# Main.net
KiCad netlist of a schematic drawn in Altium Designer
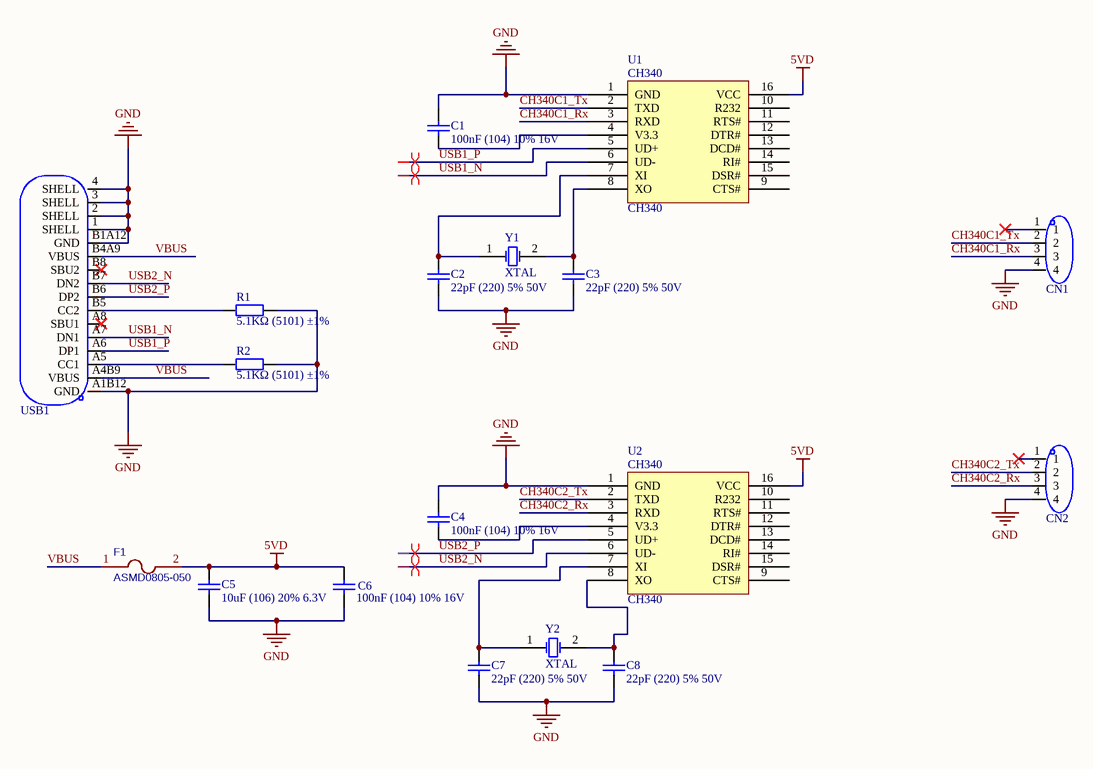
[diagram p0: Main.SchDoc]

(export (version "E")
  (design (tool "Eeschema 10.0.6"))
  (components
    (comp (ref "C1")
      (value "100nF (104) 10% 16V")
      (footprint "0402_C")
      (description "贴片电容")
      (libsource (lib "Cap") (part "0402 100nF (104) 10% 16V"))
    )
    (comp (ref "C2")
      (value "22pF (220) 5% 50V")
      (footprint "0402_C")
      (description "贴片电容")
      (libsource (lib "Miscellaneous Devices LC") (part "0402 22pF (220) 5% 50V"))
    )
    (comp (ref "C3")
      (value "22pF (220) 5% 50V")
      (footprint "0402_C")
      (description "贴片电容")
      (libsource (lib "Miscellaneous Devices LC") (part "0402 22pF (220) 5% 50V"))
    )
    (comp (ref "C4")
      (value "100nF (104) 10% 16V")
      (footprint "0402_C")
      (description "贴片电容")
      (libsource (lib "Cap") (part "0402 100nF (104) 10% 16V"))
    )
    (comp (ref "C5")
      (value "10uF (106) 20% 6.3V")
      (footprint "0402_C")
      (description "贴片电容")
      (libsource (lib "Cap") (part "0402 10uF (106) 20% 6.3V"))
    )
    (comp (ref "C6")
      (value "100nF (104) 10% 16V")
      (footprint "0402_C")
      (description "贴片电容")
      (libsource (lib "Cap") (part "0402 100nF (104) 10% 16V"))
    )
    (comp (ref "C7")
      (value "22pF (220) 5% 50V")
      (footprint "0402_C")
      (description "贴片电容")
      (libsource (lib "Miscellaneous Devices LC") (part "0402 22pF (220) 5% 50V"))
    )
    (comp (ref "C8")
      (value "22pF (220) 5% 50V")
      (footprint "0402_C")
      (description "贴片电容")
      (libsource (lib "Miscellaneous Devices LC") (part "0402 22pF (220) 5% 50V"))
    )
    (comp (ref "CN1")
      (value "1.5-4A")
      (footprint "CONN-TH_1.5-4A")
      (fields (field (name "MANUFACTURER") "CAX(创都)"))
      (libsource (lib "mysch") (part "1.5-4A"))
    )
    (comp (ref "CN2")
      (value "1.5-4A")
      (footprint "CONN-TH_1.5-4A")
      (fields (field (name "MANUFACTURER") "CAX(创都)"))
      (libsource (lib "mysch") (part "1.5-4A"))
    )
    (comp (ref "F1")
      (value "ASMD0805-050")
      (footprint "ASMD0805")
      (fields (field (name "BOM_SUPPLIER PART") "C135329") (field (name "CONTRIBUTOR") "LCSC"))
      (libsource (lib "mysch") (part "ASMD0805-050"))
    )
    (comp (ref "R1")
      (value "5.1KΩ (5101) ±1%")
      (footprint "0402_R")
      (description "贴片电阻")
      (libsource (lib "RES") (part "0402 5.1KΩ (5101) 1%"))
    )
    (comp (ref "R2")
      (value "5.1KΩ (5101) ±1%")
      (footprint "0402_R")
      (description "贴片电阻")
      (libsource (lib "RES") (part "0402 5.1KΩ (5101) 1%"))
    )
    (comp (ref "U1")
      (value "CH340")
      (footprint "SOP-16_L10.0")
      (description "USB to serial")
      (libsource (lib "mysch") (part "CH340"))
    )
    (comp (ref "U2")
      (value "CH340")
      (footprint "SOP-16_L10.0")
      (description "USB to serial")
      (libsource (lib "mysch") (part "CH340"))
    )
    (comp (ref "USB1")
      (value "TYPE-C16PIN")
      (footprint "TYPE-C-SMD")
      (fields (field (name "MANUFACTURER") "SHOU HAN(首韩)"))
      (libsource (lib "mysch") (part "TYPE-C16PIN"))
    )
    (comp (ref "Y1")
      (value "XTAL")
      (footprint "XTAL_socket")
      (description "Crystal Oscillator")
      (fields (field (name "PUBLISHER") "Altium Limited"))
      (libsource (lib "Miscellaneous Devices") (part "XTAL"))
    )
    (comp (ref "Y2")
      (value "XTAL")
      (footprint "XTAL_socket")
      (description "Crystal Oscillator")
      (fields (field (name "PUBLISHER") "Altium Limited"))
      (libsource (lib "Miscellaneous Devices") (part "XTAL"))
    )
  )
  (nets
    (net (code "1") (name "/CH340C1_Rx") (class "Default")
      (node (ref "CN1") (pin "3") (pinfunction "3_3") (pintype "passive"))
      (node (ref "U1") (pin "3") (pinfunction "RXD_3") (pintype "passive"))
    )
    (net (code "2") (name "/CH340C1_Tx") (class "Default")
      (node (ref "CN1") (pin "2") (pinfunction "2_2") (pintype "passive"))
      (node (ref "U1") (pin "2") (pinfunction "TXD_2") (pintype "passive"))
    )
    (net (code "3") (name "/CH340C2_Rx") (class "Default")
      (node (ref "CN2") (pin "3") (pinfunction "3_3") (pintype "passive"))
      (node (ref "U2") (pin "3") (pinfunction "RXD_3") (pintype "passive"))
    )
    (net (code "4") (name "/CH340C2_Tx") (class "Default")
      (node (ref "CN2") (pin "2") (pinfunction "2_2") (pintype "passive"))
      (node (ref "U2") (pin "2") (pinfunction "TXD_2") (pintype "passive"))
    )
    (net (code "5") (name "/USB1_N") (class "Default")
      (node (ref "U1") (pin "6") (pinfunction "UD-_6") (pintype "passive"))
      (node (ref "USB1") (pin "A7") (pinfunction "DN1_A7") (pintype "passive"))
    )
    (net (code "6") (name "/USB1_P") (class "Default")
      (node (ref "U1") (pin "5") (pinfunction "UD+_5") (pintype "passive"))
      (node (ref "USB1") (pin "A6") (pinfunction "DP1_A6") (pintype "passive"))
    )
    (net (code "7") (name "/USB2_N") (class "Default")
      (node (ref "U2") (pin "6") (pinfunction "UD-_6") (pintype "passive"))
      (node (ref "USB1") (pin "B7") (pinfunction "DN2_B7") (pintype "passive"))
    )
    (net (code "8") (name "/USB2_P") (class "Default")
      (node (ref "U2") (pin "5") (pinfunction "UD+_5") (pintype "passive"))
      (node (ref "USB1") (pin "B6") (pinfunction "DP2_B6") (pintype "passive"))
    )
    (net (code "9") (name "/VBUS") (class "Default")
      (node (ref "F1") (pin "1") (pinfunction "1_1") (pintype "passive"))
      (node (ref "USB1") (pin "A4B9") (pinfunction "VBUS_A4B9") (pintype "passive"))
      (node (ref "USB1") (pin "B4A9") (pinfunction "VBUS_B4A9") (pintype "passive"))
    )
    (net (code "10") (name "5VD") (class "Default")
      (node (ref "C5") (pin "2") (pinfunction "2_2") (pintype "passive"))
      (node (ref "C6") (pin "2") (pinfunction "2_2") (pintype "passive"))
      (node (ref "F1") (pin "2") (pinfunction "2_2") (pintype "passive"))
      (node (ref "U1") (pin "16") (pinfunction "VCC_16") (pintype "passive"))
      (node (ref "U2") (pin "16") (pinfunction "VCC_16") (pintype "passive"))
    )
    (net (code "11") (name "GND") (class "Default")
      (node (ref "C1") (pin "2") (pinfunction "2_2") (pintype "passive"))
      (node (ref "C2") (pin "1") (pinfunction "1_1") (pintype "passive"))
      (node (ref "C3") (pin "1") (pinfunction "1_1") (pintype "passive"))
      (node (ref "C4") (pin "2") (pinfunction "2_2") (pintype "passive"))
      (node (ref "C5") (pin "1") (pinfunction "1_1") (pintype "passive"))
      (node (ref "C6") (pin "1") (pinfunction "1_1") (pintype "passive"))
      (node (ref "C7") (pin "1") (pinfunction "1_1") (pintype "passive"))
      (node (ref "C8") (pin "1") (pinfunction "1_1") (pintype "passive"))
      (node (ref "CN1") (pin "4") (pinfunction "4_4") (pintype "passive"))
      (node (ref "CN2") (pin "4") (pinfunction "4_4") (pintype "passive"))
      (node (ref "R1") (pin "2") (pinfunction "2_2") (pintype "passive"))
      (node (ref "R2") (pin "2") (pinfunction "2_2") (pintype "passive"))
      (node (ref "U1") (pin "1") (pinfunction "GND_1") (pintype "passive"))
      (node (ref "U2") (pin "1") (pinfunction "GND_1") (pintype "passive"))
      (node (ref "USB1") (pin "1") (pinfunction "SHELL_1") (pintype "passive"))
      (node (ref "USB1") (pin "2") (pinfunction "SHELL_2") (pintype "passive"))
      (node (ref "USB1") (pin "3") (pinfunction "SHELL_3") (pintype "passive"))
      (node (ref "USB1") (pin "4") (pinfunction "SHELL_4") (pintype "passive"))
      (node (ref "USB1") (pin "A1B12") (pinfunction "GND_A1B12") (pintype "passive"))
      (node (ref "USB1") (pin "B1A12") (pinfunction "GND_B1A12") (pintype "passive"))
    )
    (net (code "12") (name "Net-(U1-V3.3)") (class "Default")
      (node (ref "C1") (pin "1") (pinfunction "1_1") (pintype "passive"))
      (node (ref "U1") (pin "4") (pinfunction "V3.3_4") (pintype "passive"))
    )
    (net (code "13") (name "Net-(U1-XI)") (class "Default")
      (node (ref "C2") (pin "2") (pinfunction "2_2") (pintype "passive"))
      (node (ref "U1") (pin "7") (pinfunction "XI_7") (pintype "passive"))
      (node (ref "Y1") (pin "1") (pinfunction "OSC1_1") (pintype "passive"))
    )
    (net (code "14") (name "Net-(U1-XO)") (class "Default")
      (node (ref "C3") (pin "2") (pinfunction "2_2") (pintype "passive"))
      (node (ref "U1") (pin "8") (pinfunction "XO_8") (pintype "passive"))
      (node (ref "Y1") (pin "2") (pinfunction "OSC2_2") (pintype "passive"))
    )
    (net (code "15") (name "Net-(U2-V3.3)") (class "Default")
      (node (ref "C4") (pin "1") (pinfunction "1_1") (pintype "passive"))
      (node (ref "U2") (pin "4") (pinfunction "V3.3_4") (pintype "passive"))
    )
    (net (code "16") (name "Net-(U2-XI)") (class "Default")
      (node (ref "C7") (pin "2") (pinfunction "2_2") (pintype "passive"))
      (node (ref "U2") (pin "7") (pinfunction "XI_7") (pintype "passive"))
      (node (ref "Y2") (pin "1") (pinfunction "OSC1_1") (pintype "passive"))
    )
    (net (code "17") (name "Net-(U2-XO)") (class "Default")
      (node (ref "C8") (pin "2") (pinfunction "2_2") (pintype "passive"))
      (node (ref "U2") (pin "8") (pinfunction "XO_8") (pintype "passive"))
      (node (ref "Y2") (pin "2") (pinfunction "OSC2_2") (pintype "passive"))
    )
    (net (code "18") (name "Net-(USB1-CC1)") (class "Default")
      (node (ref "R2") (pin "1") (pinfunction "1_1") (pintype "passive"))
      (node (ref "USB1") (pin "A5") (pinfunction "CC1_A5") (pintype "passive"))
    )
    (net (code "19") (name "Net-(USB1-CC2)") (class "Default")
      (node (ref "R1") (pin "1") (pinfunction "1_1") (pintype "passive"))
      (node (ref "USB1") (pin "B5") (pinfunction "CC2_B5") (pintype "passive"))
    )
    (net (code "20") (name "unconnected-(CN1-Pad1)") (class "Default")
      (node (ref "CN1") (pin "1") (pinfunction "1_1") (pintype "passive+no_connect"))
    )
    (net (code "21") (name "unconnected-(CN2-Pad1)") (class "Default")
      (node (ref "CN2") (pin "1") (pinfunction "1_1") (pintype "passive+no_connect"))
    )
    (net (code "22") (name "unconnected-(U1-CTS#-Pad9)") (class "Default")
      (node (ref "U1") (pin "9") (pinfunction "CTS#_9") (pintype "passive"))
    )
    (net (code "23") (name "unconnected-(U1-DCD#-Pad13)") (class "Default")
      (node (ref "U1") (pin "13") (pinfunction "DCD#_13") (pintype "passive"))
    )
    (net (code "24") (name "unconnected-(U1-DSR#-Pad15)") (class "Default")
      (node (ref "U1") (pin "15") (pinfunction "DSR#_15") (pintype "passive"))
    )
    (net (code "25") (name "unconnected-(U1-DTR#-Pad12)") (class "Default")
      (node (ref "U1") (pin "12") (pinfunction "DTR#_12") (pintype "passive"))
    )
    (net (code "26") (name "unconnected-(U1-R232-Pad10)") (class "Default")
      (node (ref "U1") (pin "10") (pinfunction "R232_10") (pintype "passive"))
    )
    (net (code "27") (name "unconnected-(U1-RI#-Pad14)") (class "Default")
      (node (ref "U1") (pin "14") (pinfunction "RI#_14") (pintype "passive"))
    )
    (net (code "28") (name "unconnected-(U1-RTS#-Pad11)") (class "Default")
      (node (ref "U1") (pin "11") (pinfunction "RTS#_11") (pintype "passive"))
    )
    (net (code "29") (name "unconnected-(U2-CTS#-Pad9)") (class "Default")
      (node (ref "U2") (pin "9") (pinfunction "CTS#_9") (pintype "passive"))
    )
    (net (code "30") (name "unconnected-(U2-DCD#-Pad13)") (class "Default")
      (node (ref "U2") (pin "13") (pinfunction "DCD#_13") (pintype "passive"))
    )
    (net (code "31") (name "unconnected-(U2-DSR#-Pad15)") (class "Default")
      (node (ref "U2") (pin "15") (pinfunction "DSR#_15") (pintype "passive"))
    )
    (net (code "32") (name "unconnected-(U2-DTR#-Pad12)") (class "Default")
      (node (ref "U2") (pin "12") (pinfunction "DTR#_12") (pintype "passive"))
    )
    (net (code "33") (name "unconnected-(U2-R232-Pad10)") (class "Default")
      (node (ref "U2") (pin "10") (pinfunction "R232_10") (pintype "passive"))
    )
    (net (code "34") (name "unconnected-(U2-RI#-Pad14)") (class "Default")
      (node (ref "U2") (pin "14") (pinfunction "RI#_14") (pintype "passive"))
    )
    (net (code "35") (name "unconnected-(U2-RTS#-Pad11)") (class "Default")
      (node (ref "U2") (pin "11") (pinfunction "RTS#_11") (pintype "passive"))
    )
    (net (code "36") (name "unconnected-(USB1-SBU1-PadA8)") (class "Default")
      (node (ref "USB1") (pin "A8") (pinfunction "SBU1_A8") (pintype "passive+no_connect"))
    )
    (net (code "37") (name "unconnected-(USB1-SBU2-PadB8)") (class "Default")
      (node (ref "USB1") (pin "B8") (pinfunction "SBU2_B8") (pintype "passive+no_connect"))
    )
  )
)
